# ESPREMOTE.net
KiCad netlist of a schematic drawn in EAGLE
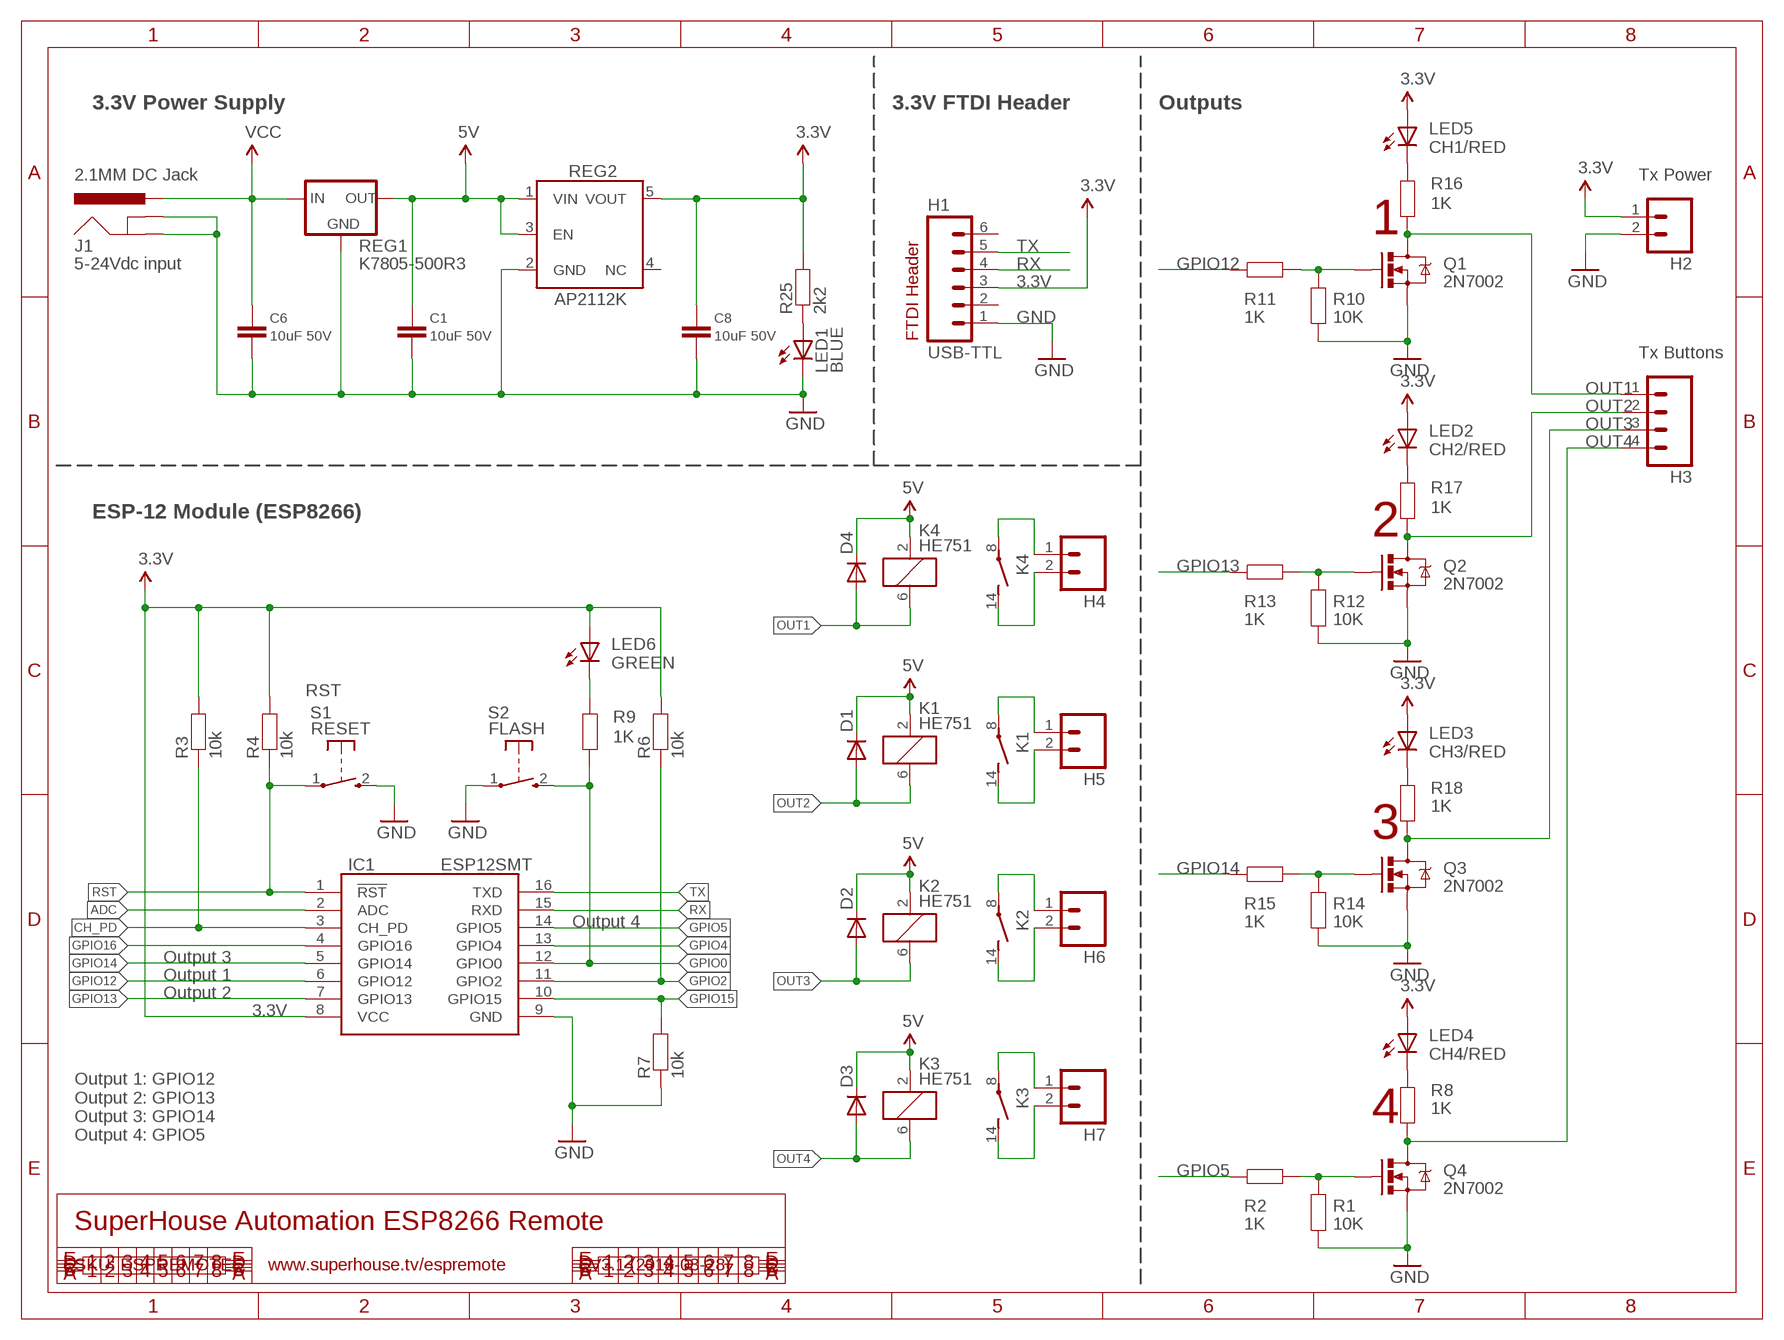
[diagram p0: schematic, sheet 1]

(export (version "E")
  (design (tool "Eeschema 10.0.6"))
  (components
    (comp (ref "C1")
      (value "10uF 50V")
      (footprint "eagle-import:C0805")
      (libsource (lib "eagle-import") (part "C-EUC0805"))
    )
    (comp (ref "C6")
      (value "10uF 50V")
      (footprint "eagle-import:C0805")
      (libsource (lib "eagle-import") (part "C-EUC0805"))
    )
    (comp (ref "C8")
      (value "10uF 50V")
      (footprint "eagle-import:C0805")
      (libsource (lib "eagle-import") (part "C-EUC0805"))
    )
    (comp (ref "D1")
      (value "DIODESMA")
      (footprint "eagle-import:SMA-DIODE")
      (libsource (lib "eagle-import") (part "DIODESMA"))
    )
    (comp (ref "D2")
      (value "DIODESMA")
      (footprint "eagle-import:SMA-DIODE")
      (libsource (lib "eagle-import") (part "DIODESMA"))
    )
    (comp (ref "D3")
      (value "DIODESMA")
      (footprint "eagle-import:SMA-DIODE")
      (libsource (lib "eagle-import") (part "DIODESMA"))
    )
    (comp (ref "D4")
      (value "DIODESMA")
      (footprint "eagle-import:SMA-DIODE")
      (libsource (lib "eagle-import") (part "DIODESMA"))
    )
    (comp (ref "H1")
      (value "USB-TTL")
      (footprint "eagle-import:1X06")
      (libsource (lib "eagle-import") (part "M06SIP"))
    )
    (comp (ref "H2")
      (value "M02PTH")
      (footprint "eagle-import:1X02")
      (libsource (lib "eagle-import") (part "M02PTH"))
    )
    (comp (ref "H3")
      (value "M04PTH")
      (footprint "eagle-import:1X04")
      (libsource (lib "eagle-import") (part "M04PTH"))
    )
    (comp (ref "H4")
      (value "M02PTH")
      (footprint "eagle-import:1X02")
      (libsource (lib "eagle-import") (part "M02PTH"))
    )
    (comp (ref "H5")
      (value "M02PTH")
      (footprint "eagle-import:1X02")
      (libsource (lib "eagle-import") (part "M02PTH"))
    )
    (comp (ref "H6")
      (value "M02PTH")
      (footprint "eagle-import:1X02")
      (libsource (lib "eagle-import") (part "M02PTH"))
    )
    (comp (ref "H7")
      (value "M02PTH")
      (footprint "eagle-import:1X02")
      (libsource (lib "eagle-import") (part "M02PTH"))
    )
    (comp (ref "IC1")
      (value "ESP12SMT")
      (footprint "eagle-import:ESP12")
      (libsource (lib "eagle-import") (part "ESP12SMT"))
    )
    (comp (ref "J1")
      (value "2.1MM DC Jack")
      (footprint "eagle-import:POWER_JACK_PTH_SLOTS")
      (libsource (lib "eagle-import") (part "POWER_JACKPTH_SLOTS"))
    )
    (comp (ref "K1")
      (value "HE751")
      (footprint "eagle-import:HE751")
      (libsource (lib "eagle-import") (part "HE751"))
    )
    (comp (ref "K2")
      (value "HE751")
      (footprint "eagle-import:HE751")
      (libsource (lib "eagle-import") (part "HE751"))
    )
    (comp (ref "K3")
      (value "HE751")
      (footprint "eagle-import:HE751")
      (libsource (lib "eagle-import") (part "HE751"))
    )
    (comp (ref "K4")
      (value "HE751")
      (footprint "eagle-import:HE751")
      (libsource (lib "eagle-import") (part "HE751"))
    )
    (comp (ref "LED1")
      (value "BLUE")
      (footprint "eagle-import:LED-0603")
      (libsource (lib "eagle-import") (part "LED0603"))
    )
    (comp (ref "LED2")
      (value "CH2/RED")
      (footprint "eagle-import:LED-0603")
      (libsource (lib "eagle-import") (part "freetronics-master-v1_LED0603"))
    )
    (comp (ref "LED3")
      (value "CH3/RED")
      (footprint "eagle-import:LED-0603")
      (libsource (lib "eagle-import") (part "freetronics-master-v1_LED0603"))
    )
    (comp (ref "LED4")
      (value "CH4/RED")
      (footprint "eagle-import:LED-0603")
      (libsource (lib "eagle-import") (part "freetronics-master-v1_LED0603"))
    )
    (comp (ref "LED5")
      (value "CH1/RED")
      (footprint "eagle-import:LED-0603")
      (libsource (lib "eagle-import") (part "freetronics-master-v1_LED0603"))
    )
    (comp (ref "LED6")
      (value "GREEN")
      (footprint "eagle-import:LED-0603")
      (libsource (lib "eagle-import") (part "freetronics-master-v1_LED0603"))
    )
    (comp (ref "Q1")
      (value "2N7002")
      (footprint "eagle-import:SOT23-3")
      (libsource (lib "eagle-import") (part "MOSFET-NCHANNELSMD"))
    )
    (comp (ref "Q2")
      (value "2N7002")
      (footprint "eagle-import:SOT23-3")
      (libsource (lib "eagle-import") (part "MOSFET-NCHANNELSMD"))
    )
    (comp (ref "Q3")
      (value "2N7002")
      (footprint "eagle-import:SOT23-3")
      (libsource (lib "eagle-import") (part "MOSFET-NCHANNELSMD"))
    )
    (comp (ref "Q4")
      (value "2N7002")
      (footprint "eagle-import:SOT23-3")
      (libsource (lib "eagle-import") (part "MOSFET-NCHANNELSMD"))
    )
    (comp (ref "R1")
      (value "10K")
      (footprint "eagle-import:0603")
      (libsource (lib "eagle-import") (part "freetronics-master-v1_RESISTOR0603"))
    )
    (comp (ref "R2")
      (value "1K")
      (footprint "eagle-import:0603")
      (libsource (lib "eagle-import") (part "freetronics-master-v1_RESISTOR0603"))
    )
    (comp (ref "R3")
      (value "10k")
      (footprint "eagle-import:0603")
      (libsource (lib "eagle-import") (part "RESISTOR0603"))
    )
    (comp (ref "R4")
      (value "10k")
      (footprint "eagle-import:0603")
      (libsource (lib "eagle-import") (part "RESISTOR0603"))
    )
    (comp (ref "R6")
      (value "10k")
      (footprint "eagle-import:0603")
      (libsource (lib "eagle-import") (part "RESISTOR0603"))
    )
    (comp (ref "R7")
      (value "10k")
      (footprint "eagle-import:0603")
      (libsource (lib "eagle-import") (part "RESISTOR0603"))
    )
    (comp (ref "R8")
      (value "1K")
      (footprint "eagle-import:0603")
      (libsource (lib "eagle-import") (part "freetronics-master-v1_RESISTOR0603"))
    )
    (comp (ref "R9")
      (value "1K")
      (footprint "eagle-import:0603")
      (libsource (lib "eagle-import") (part "freetronics-master-v1_RESISTOR0603"))
    )
    (comp (ref "R10")
      (value "10K")
      (footprint "eagle-import:0603")
      (libsource (lib "eagle-import") (part "freetronics-master-v1_RESISTOR0603"))
    )
    (comp (ref "R11")
      (value "1K")
      (footprint "eagle-import:0603")
      (libsource (lib "eagle-import") (part "freetronics-master-v1_RESISTOR0603"))
    )
    (comp (ref "R12")
      (value "10K")
      (footprint "eagle-import:0603")
      (libsource (lib "eagle-import") (part "freetronics-master-v1_RESISTOR0603"))
    )
    (comp (ref "R13")
      (value "1K")
      (footprint "eagle-import:0603")
      (libsource (lib "eagle-import") (part "freetronics-master-v1_RESISTOR0603"))
    )
    (comp (ref "R14")
      (value "10K")
      (footprint "eagle-import:0603")
      (libsource (lib "eagle-import") (part "freetronics-master-v1_RESISTOR0603"))
    )
    (comp (ref "R15")
      (value "1K")
      (footprint "eagle-import:0603")
      (libsource (lib "eagle-import") (part "freetronics-master-v1_RESISTOR0603"))
    )
    (comp (ref "R16")
      (value "1K")
      (footprint "eagle-import:0603")
      (libsource (lib "eagle-import") (part "freetronics-master-v1_RESISTOR0603"))
    )
    (comp (ref "R17")
      (value "1K")
      (footprint "eagle-import:0603")
      (libsource (lib "eagle-import") (part "freetronics-master-v1_RESISTOR0603"))
    )
    (comp (ref "R18")
      (value "1K")
      (footprint "eagle-import:0603")
      (libsource (lib "eagle-import") (part "freetronics-master-v1_RESISTOR0603"))
    )
    (comp (ref "R25")
      (value "2k2")
      (footprint "eagle-import:0603")
      (libsource (lib "eagle-import") (part "RESISTOR0603"))
    )
    (comp (ref "REG1")
      (value "K7805-500R3")
      (footprint "eagle-import:K78XX-500R3")
      (libsource (lib "eagle-import") (part "K78XX-500R3"))
    )
    (comp (ref "REG2")
      (value "AP2112KSOT25")
      (footprint "eagle-import:SOT23-5")
      (libsource (lib "eagle-import") (part "AP2112KSOT25"))
    )
    (comp (ref "S1")
      (value "RESET")
      (footprint "eagle-import:TACTILE_SWITCH_SMD_2PIN_TINY")
      (libsource (lib "eagle-import") (part "TAC_SWITCH_2PINSMT"))
    )
    (comp (ref "S2")
      (value "FLASH")
      (footprint "eagle-import:TACTILE_SWITCH_SMD_2PIN_TINY")
      (libsource (lib "eagle-import") (part "TAC_SWITCH_2PINSMT"))
    )
  )
  (nets
    (net (code "1") (name "3.3V") (class "Default")
      (node (ref "C8") (pin "1") (pinfunction "1_1") (pintype "passive"))
      (node (ref "H1") (pin "3") (pinfunction "3_3") (pintype "passive"))
      (node (ref "H2") (pin "1") (pinfunction "1_1") (pintype "passive"))
      (node (ref "IC1") (pin "8") (pinfunction "VCC_8") (pintype "power_in"))
      (node (ref "LED2") (pin "A") (pinfunction "A_A") (pintype "passive"))
      (node (ref "LED3") (pin "A") (pinfunction "A_A") (pintype "passive"))
      (node (ref "LED4") (pin "A") (pinfunction "A_A") (pintype "passive"))
      (node (ref "LED5") (pin "A") (pinfunction "A_A") (pintype "passive"))
      (node (ref "LED6") (pin "A") (pinfunction "A_A") (pintype "passive"))
      (node (ref "R25") (pin "2") (pinfunction "2_2") (pintype "passive"))
      (node (ref "R3") (pin "2") (pinfunction "2_2") (pintype "passive"))
      (node (ref "R4") (pin "2") (pinfunction "2_2") (pintype "passive"))
      (node (ref "R6") (pin "2") (pinfunction "2_2") (pintype "passive"))
      (node (ref "REG2") (pin "5") (pinfunction "VOUT_5") (pintype "bidirectional"))
    )
    (net (code "2") (name "5V") (class "Default")
      (node (ref "C1") (pin "1") (pinfunction "1_1") (pintype "passive"))
      (node (ref "D1") (pin "C") (pinfunction "C_C") (pintype "passive"))
      (node (ref "D2") (pin "C") (pinfunction "C_C") (pintype "passive"))
      (node (ref "D3") (pin "C") (pinfunction "C_C") (pintype "passive"))
      (node (ref "D4") (pin "C") (pinfunction "C_C") (pintype "passive"))
      (node (ref "K1") (pin "2") (pinfunction "1_2") (pintype "passive"))
      (node (ref "K2") (pin "2") (pinfunction "1_2") (pintype "passive"))
      (node (ref "K3") (pin "2") (pinfunction "1_2") (pintype "passive"))
      (node (ref "K4") (pin "2") (pinfunction "1_2") (pintype "passive"))
      (node (ref "REG1") (pin "3") (pinfunction "OUT_3") (pintype "output"))
      (node (ref "REG2") (pin "1") (pinfunction "VIN_1") (pintype "bidirectional"))
      (node (ref "REG2") (pin "3") (pinfunction "EN_3") (pintype "bidirectional"))
    )
    (net (code "3") (name "ADC") (class "Default")
      (node (ref "IC1") (pin "2") (pinfunction "ADC_2") (pintype "input"))
    )
    (net (code "4") (name "CH_PD") (class "Default")
      (node (ref "IC1") (pin "3") (pinfunction "CH_PD_3") (pintype "input"))
      (node (ref "R3") (pin "1") (pinfunction "1_1") (pintype "passive"))
    )
    (net (code "5") (name "GND") (class "Default")
      (node (ref "C1") (pin "2") (pinfunction "2_2") (pintype "passive"))
      (node (ref "C6") (pin "2") (pinfunction "2_2") (pintype "passive"))
      (node (ref "C8") (pin "2") (pinfunction "2_2") (pintype "passive"))
      (node (ref "H1") (pin "1") (pinfunction "1_1") (pintype "passive"))
      (node (ref "H2") (pin "2") (pinfunction "2_2") (pintype "passive"))
      (node (ref "IC1") (pin "9") (pinfunction "GND_9") (pintype "power_in"))
      (node (ref "J1") (pin "GND") (pinfunction "GND_GND") (pintype "bidirectional"))
      (node (ref "J1") (pin "GNDBREAK") (pinfunction "GNDBREAK_GNDBREAK") (pintype "bidirectional"))
      (node (ref "LED1") (pin "C") (pinfunction "C_C") (pintype "passive"))
      (node (ref "Q1") (pin "2") (pinfunction "S_2") (pintype "passive"))
      (node (ref "Q2") (pin "2") (pinfunction "S_2") (pintype "passive"))
      (node (ref "Q3") (pin "2") (pinfunction "S_2") (pintype "passive"))
      (node (ref "Q4") (pin "2") (pinfunction "S_2") (pintype "passive"))
      (node (ref "R1") (pin "1") (pinfunction "1_1") (pintype "passive"))
      (node (ref "R10") (pin "1") (pinfunction "1_1") (pintype "passive"))
      (node (ref "R12") (pin "1") (pinfunction "1_1") (pintype "passive"))
      (node (ref "R14") (pin "1") (pinfunction "1_1") (pintype "passive"))
      (node (ref "R7") (pin "1") (pinfunction "1_1") (pintype "passive"))
      (node (ref "REG1") (pin "2") (pinfunction "GND_2") (pintype "input"))
      (node (ref "REG2") (pin "2") (pinfunction "GND_2") (pintype "bidirectional"))
      (node (ref "S1") (pin "2") (pinfunction "S_2") (pintype "passive"))
      (node (ref "S2") (pin "1") (pinfunction "P_1") (pintype "passive"))
    )
    (net (code "6") (name "GPIO0") (class "Default")
      (node (ref "IC1") (pin "12") (pinfunction "GPIO0_12") (pintype "bidirectional"))
      (node (ref "R9") (pin "2") (pinfunction "2_2") (pintype "passive"))
      (node (ref "S2") (pin "2") (pinfunction "S_2") (pintype "passive"))
    )
    (net (code "7") (name "GPIO2") (class "Default")
      (node (ref "IC1") (pin "11") (pinfunction "GPIO2_11") (pintype "bidirectional"))
      (node (ref "R6") (pin "1") (pinfunction "1_1") (pintype "passive"))
    )
    (net (code "8") (name "GPIO4") (class "Default")
      (node (ref "IC1") (pin "13") (pinfunction "GPIO4_13") (pintype "bidirectional"))
    )
    (net (code "9") (name "GPIO5") (class "Default")
      (node (ref "IC1") (pin "14") (pinfunction "GPIO5_14") (pintype "bidirectional"))
      (node (ref "R2") (pin "2") (pinfunction "2_2") (pintype "passive"))
    )
    (net (code "10") (name "GPIO12") (class "Default")
      (node (ref "IC1") (pin "6") (pinfunction "GPIO12_6") (pintype "bidirectional"))
      (node (ref "R11") (pin "2") (pinfunction "2_2") (pintype "passive"))
    )
    (net (code "11") (name "GPIO13") (class "Default")
      (node (ref "IC1") (pin "7") (pinfunction "GPIO13_7") (pintype "bidirectional"))
      (node (ref "R13") (pin "2") (pinfunction "2_2") (pintype "passive"))
    )
    (net (code "12") (name "GPIO14") (class "Default")
      (node (ref "IC1") (pin "5") (pinfunction "GPIO14_5") (pintype "bidirectional"))
      (node (ref "R15") (pin "2") (pinfunction "2_2") (pintype "passive"))
    )
    (net (code "13") (name "GPIO15") (class "Default")
      (node (ref "IC1") (pin "10") (pinfunction "GPIO15_10") (pintype "bidirectional"))
      (node (ref "R7") (pin "2") (pinfunction "2_2") (pintype "passive"))
    )
    (net (code "14") (name "GPIO16") (class "Default")
      (node (ref "IC1") (pin "4") (pinfunction "GPIO16_4") (pintype "bidirectional"))
    )
    (net (code "15") (name "Net-(K1B-P)") (class "Default")
      (node (ref "H5") (pin "1") (pinfunction "1_1") (pintype "passive"))
      (node (ref "K1") (pin "8") (pinfunction "P_8") (pintype "passive"))
    )
    (net (code "16") (name "Net-(K1B-S)") (class "Default")
      (node (ref "H5") (pin "2") (pinfunction "2_2") (pintype "passive"))
      (node (ref "K1") (pin "14") (pinfunction "S_14") (pintype "passive"))
    )
    (net (code "17") (name "Net-(K2B-P)") (class "Default")
      (node (ref "H6") (pin "1") (pinfunction "1_1") (pintype "passive"))
      (node (ref "K2") (pin "8") (pinfunction "P_8") (pintype "passive"))
    )
    (net (code "18") (name "Net-(K2B-S)") (class "Default")
      (node (ref "H6") (pin "2") (pinfunction "2_2") (pintype "passive"))
      (node (ref "K2") (pin "14") (pinfunction "S_14") (pintype "passive"))
    )
    (net (code "19") (name "Net-(K3B-P)") (class "Default")
      (node (ref "H7") (pin "1") (pinfunction "1_1") (pintype "passive"))
      (node (ref "K3") (pin "8") (pinfunction "P_8") (pintype "passive"))
    )
    (net (code "20") (name "Net-(K3B-S)") (class "Default")
      (node (ref "H7") (pin "2") (pinfunction "2_2") (pintype "passive"))
      (node (ref "K3") (pin "14") (pinfunction "S_14") (pintype "passive"))
    )
    (net (code "21") (name "Net-(K4B-P)") (class "Default")
      (node (ref "H4") (pin "1") (pinfunction "1_1") (pintype "passive"))
      (node (ref "K4") (pin "8") (pinfunction "P_8") (pintype "passive"))
    )
    (net (code "22") (name "Net-(K4B-S)") (class "Default")
      (node (ref "H4") (pin "2") (pinfunction "2_2") (pintype "passive"))
      (node (ref "K4") (pin "14") (pinfunction "S_14") (pintype "passive"))
    )
    (net (code "23") (name "Net-(LED1-PadA)") (class "Default")
      (node (ref "LED1") (pin "A") (pinfunction "A_A") (pintype "passive"))
      (node (ref "R25") (pin "1") (pinfunction "1_1") (pintype "passive"))
    )
    (net (code "24") (name "Net-(LED2-PadC)") (class "Default")
      (node (ref "LED2") (pin "C") (pinfunction "C_C") (pintype "passive"))
      (node (ref "R17") (pin "1") (pinfunction "1_1") (pintype "passive"))
    )
    (net (code "25") (name "Net-(LED3-PadC)") (class "Default")
      (node (ref "LED3") (pin "C") (pinfunction "C_C") (pintype "passive"))
      (node (ref "R18") (pin "1") (pinfunction "1_1") (pintype "passive"))
    )
    (net (code "26") (name "Net-(LED4-PadC)") (class "Default")
      (node (ref "LED4") (pin "C") (pinfunction "C_C") (pintype "passive"))
      (node (ref "R8") (pin "1") (pinfunction "1_1") (pintype "passive"))
    )
    (net (code "27") (name "Net-(LED5-PadC)") (class "Default")
      (node (ref "LED5") (pin "C") (pinfunction "C_C") (pintype "passive"))
      (node (ref "R16") (pin "1") (pinfunction "1_1") (pintype "passive"))
    )
    (net (code "28") (name "Net-(LED6-PadC)") (class "Default")
      (node (ref "LED6") (pin "C") (pinfunction "C_C") (pintype "passive"))
      (node (ref "R9") (pin "1") (pinfunction "1_1") (pintype "passive"))
    )
    (net (code "29") (name "Net-(Q1-G)") (class "Default")
      (node (ref "Q1") (pin "1") (pinfunction "G_1") (pintype "passive"))
      (node (ref "R10") (pin "2") (pinfunction "2_2") (pintype "passive"))
      (node (ref "R11") (pin "1") (pinfunction "1_1") (pintype "passive"))
    )
    (net (code "30") (name "Net-(Q2-G)") (class "Default")
      (node (ref "Q2") (pin "1") (pinfunction "G_1") (pintype "passive"))
      (node (ref "R12") (pin "2") (pinfunction "2_2") (pintype "passive"))
      (node (ref "R13") (pin "1") (pinfunction "1_1") (pintype "passive"))
    )
    (net (code "31") (name "Net-(Q3-G)") (class "Default")
      (node (ref "Q3") (pin "1") (pinfunction "G_1") (pintype "passive"))
      (node (ref "R14") (pin "2") (pinfunction "2_2") (pintype "passive"))
      (node (ref "R15") (pin "1") (pinfunction "1_1") (pintype "passive"))
    )
    (net (code "32") (name "Net-(Q4-G)") (class "Default")
      (node (ref "Q4") (pin "1") (pinfunction "G_1") (pintype "passive"))
      (node (ref "R1") (pin "2") (pinfunction "2_2") (pintype "passive"))
      (node (ref "R2") (pin "1") (pinfunction "1_1") (pintype "passive"))
    )
    (net (code "33") (name "OUT1") (class "Default")
      (node (ref "D4") (pin "A") (pinfunction "A_A") (pintype "passive"))
      (node (ref "H3") (pin "1") (pinfunction "1_1") (pintype "passive"))
      (node (ref "K4") (pin "6") (pinfunction "2_6") (pintype "passive"))
      (node (ref "Q1") (pin "3") (pinfunction "D_3") (pintype "passive"))
      (node (ref "R16") (pin "2") (pinfunction "2_2") (pintype "passive"))
    )
    (net (code "34") (name "OUT2") (class "Default")
      (node (ref "D1") (pin "A") (pinfunction "A_A") (pintype "passive"))
      (node (ref "H3") (pin "2") (pinfunction "2_2") (pintype "passive"))
      (node (ref "K1") (pin "6") (pinfunction "2_6") (pintype "passive"))
      (node (ref "Q2") (pin "3") (pinfunction "D_3") (pintype "passive"))
      (node (ref "R17") (pin "2") (pinfunction "2_2") (pintype "passive"))
    )
    (net (code "35") (name "OUT3") (class "Default")
      (node (ref "D2") (pin "A") (pinfunction "A_A") (pintype "passive"))
      (node (ref "H3") (pin "3") (pinfunction "3_3") (pintype "passive"))
      (node (ref "K2") (pin "6") (pinfunction "2_6") (pintype "passive"))
      (node (ref "Q3") (pin "3") (pinfunction "D_3") (pintype "passive"))
      (node (ref "R18") (pin "2") (pinfunction "2_2") (pintype "passive"))
    )
    (net (code "36") (name "OUT4") (class "Default")
      (node (ref "D3") (pin "A") (pinfunction "A_A") (pintype "passive"))
      (node (ref "H3") (pin "4") (pinfunction "4_4") (pintype "passive"))
      (node (ref "K3") (pin "6") (pinfunction "2_6") (pintype "passive"))
      (node (ref "Q4") (pin "3") (pinfunction "D_3") (pintype "passive"))
      (node (ref "R8") (pin "2") (pinfunction "2_2") (pintype "passive"))
    )
    (net (code "37") (name "RST") (class "Default")
      (node (ref "IC1") (pin "1") (pinfunction "~{RST}_1") (pintype "bidirectional"))
      (node (ref "R4") (pin "1") (pinfunction "1_1") (pintype "passive"))
      (node (ref "S1") (pin "1") (pinfunction "P_1") (pintype "passive"))
    )
    (net (code "38") (name "RX") (class "Default")
      (node (ref "H1") (pin "4") (pinfunction "4_4") (pintype "passive"))
      (node (ref "IC1") (pin "15") (pinfunction "RXD_15") (pintype "input"))
    )
    (net (code "39") (name "TX") (class "Default")
      (node (ref "H1") (pin "5") (pinfunction "5_5") (pintype "passive"))
      (node (ref "IC1") (pin "16") (pinfunction "TXD_16") (pintype "output"))
    )
    (net (code "40") (name "VCC") (class "Default")
      (node (ref "C6") (pin "1") (pinfunction "1_1") (pintype "passive"))
      (node (ref "J1") (pin "PWR") (pinfunction "PWR_PWR") (pintype "bidirectional"))
      (node (ref "REG1") (pin "1") (pinfunction "IN_1") (pintype "input"))
    )
    (net (code "41") (name "unconnected-(H1-Pad2)") (class "Default")
      (node (ref "H1") (pin "2") (pinfunction "2_2") (pintype "passive"))
    )
    (net (code "42") (name "unconnected-(H1-Pad6)") (class "Default")
      (node (ref "H1") (pin "6") (pinfunction "6_6") (pintype "passive"))
    )
    (net (code "43") (name "unconnected-(REG2-NC-Pad4)") (class "Default")
      (node (ref "REG2") (pin "4") (pinfunction "NC_4") (pintype "bidirectional"))
    )
  )
)
